# Heatbed-MK24.net
KiCad netlist of a schematic drawn in EAGLE
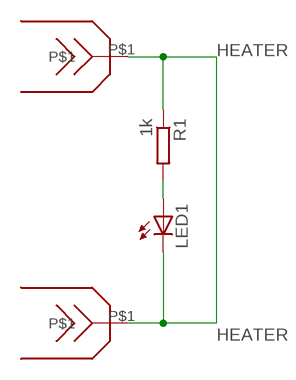
[diagram p0: schematic, sheet 1]

(export (version "E")
  (design (tool "Eeschema 10.0.6"))
  (components
    (comp (ref "LED1")
      (value "LEDCHIPLED_0805")
      (footprint "eagle-import:CHIPLED_0805")
      (libsource (lib "eagle-import") (part "LEDCHIPLED_0805"))
    )
    (comp (ref "R1")
      (value "1k")
      (footprint "eagle-import:M0805")
      (libsource (lib "eagle-import") (part "R-EU_M0805"))
    )
    (comp (ref "U$1")
      (value "FASTONSMD")
      (footprint "eagle-import:FASTONSMD")
      (libsource (lib "eagle-import") (part "FASTONSMD"))
    )
    (comp (ref "U$2")
      (value "FASTONSMD")
      (footprint "eagle-import:FASTONSMD")
      (libsource (lib "eagle-import") (part "FASTONSMD"))
    )
  )
  (nets
    (net (code "1") (name "/HEATER") (class "Default")
      (node (ref "LED1") (pin "C") (pinfunction "C_C") (pintype "passive"))
      (node (ref "R1") (pin "1") (pinfunction "1_1") (pintype "passive"))
      (node (ref "U$1") (pin "P$1") (pinfunction "P$1_P$1") (pintype "bidirectional"))
      (node (ref "U$2") (pin "P$1") (pinfunction "P$1_P$1") (pintype "bidirectional"))
    )
    (net (code "2") (name "Net-(LED1-PadA)") (class "Default")
      (node (ref "LED1") (pin "A") (pinfunction "A_A") (pintype "passive"))
      (node (ref "R1") (pin "2") (pinfunction "2_2") (pintype "passive"))
    )
  )
)
